# bqZUM_UsbBtAdapter.net
KiCad netlist of a schematic drawn in Altium Designer
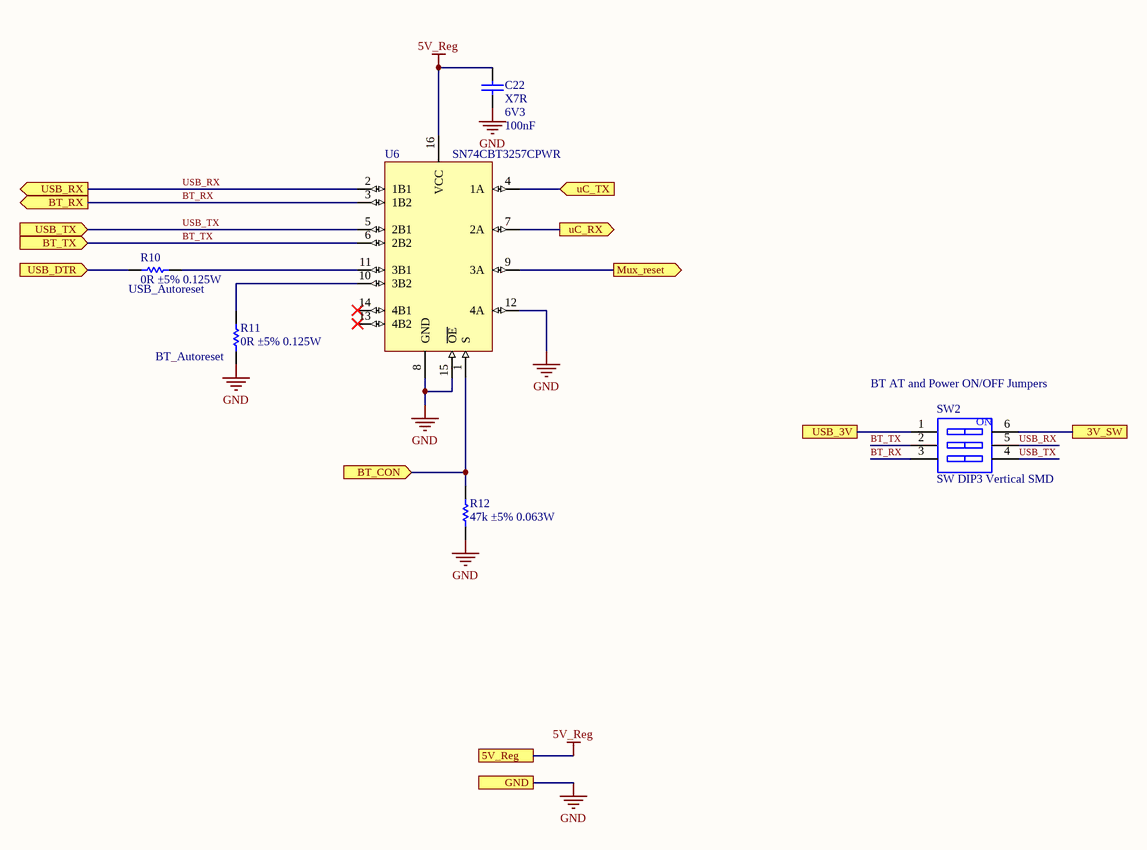
[diagram p0: bqZUM_UsbBtAdapter.SchDoc]

(export (version "E")
  (design (tool "Eeschema 10.0.6"))
  (components
    (comp (ref "C22")
      (value "Capacitor")
      (footprint "C0402")
      (fields
        (field (name "DIELECTRIC") "X7R")
        (field (name "VOLTAGE") "6V3")
        (field (name "CAPACITANCE") "100nF")
        (field (name "PART NUMBER") "C0402_100nF_6V3_±10%")
        (field (name "TOLERANCE") "±10%")
        (field (name "MANUFACTURER") "Kemet")
      )
      (libsource (lib "Pasives_Capacitor_SMD") (part "Capacitor"))
    )
    (comp (ref "R10")
      (value "0R ±5% 0.125W")
      (footprint "R0805")
      (description "Resistor")
      (fields (field (name "TOLERANCE") "±5%") (field (name "POWER") "0.125W"))
      (libsource (lib "Pasives_Resistor_SMD") (part "Resistor"))
    )
    (comp (ref "R11")
      (value "0R ±5% 0.125W")
      (footprint "R0805")
      (description "Resistor")
      (fields (field (name "TOLERANCE") "±5%") (field (name "POWER") "0.125W"))
      (libsource (lib "Pasives_Resistor_SMD") (part "Resistor"))
    )
    (comp (ref "R12")
      (value "47k ±5% 0.063W")
      (footprint "R0402")
      (description "Resistor")
      (fields (field (name "TOLERANCE") "±5%") (field (name "POWER") "0.063W"))
      (libsource (lib "Pasives_Resistor_SMD") (part "Resistor"))
    )
    (comp (ref "SW2")
      (value "SW DIP3 Vertical SMD")
      (footprint "SW DIP3 SMD 1.27")
      (description "SWITCH TAPE SEAL 3 POS SMD")
      (fields (field (name "PART NUMBER") "SW-DIP 3 SMD") (field (name "MANUFACTURER") "Würth Elektronik"))
      (libsource (lib "Electromechanical") (part "SW DIP3 Vertical SMD"))
    )
    (comp (ref "U6")
      (value "SN74CBT3257CPWR")
      (footprint "TSSOP16")
      (description "4-bit 1-of-2 FET multiplexer/demultiplexer")
      (fields (field (name "PART NUMBER") "SN74CBT3257") (field (name "MANUFACTURER") "Texas Instruments"))
      (libsource (lib "Semiconductors_Logic_Gate") (part "SN74CBT3257"))
    )
  )
  (nets
    (net (code "1") (name "/3V_SW") (class "Default")
      (node (ref "SW2") (pin "6") (pinfunction "6_6") (pintype "passive"))
    )
    (net (code "2") (name "/BT_CON") (class "Default")
      (node (ref "R12") (pin "2") (pinfunction "2_2") (pintype "passive"))
      (node (ref "U6") (pin "1") (pinfunction "S_1") (pintype "input"))
    )
    (net (code "3") (name "/BT_RX") (class "Default")
      (node (ref "SW2") (pin "3") (pinfunction "3_3") (pintype "passive"))
      (node (ref "U6") (pin "3") (pinfunction "1B2_3") (pintype "bidirectional"))
    )
    (net (code "4") (name "/BT_TX") (class "Default")
      (node (ref "SW2") (pin "2") (pinfunction "2_2") (pintype "passive"))
      (node (ref "U6") (pin "6") (pinfunction "2B2_6") (pintype "bidirectional"))
    )
    (net (code "5") (name "/Mux_reset") (class "Default")
      (node (ref "U6") (pin "9") (pinfunction "3A_9") (pintype "bidirectional"))
    )
    (net (code "6") (name "/USB_3V") (class "Default")
      (node (ref "SW2") (pin "1") (pinfunction "1_1") (pintype "passive"))
    )
    (net (code "7") (name "/USB_DTR") (class "Default")
      (node (ref "R10") (pin "1") (pinfunction "1_1") (pintype "passive"))
    )
    (net (code "8") (name "/USB_RX") (class "Default")
      (node (ref "SW2") (pin "5") (pinfunction "5_5") (pintype "passive"))
      (node (ref "U6") (pin "2") (pinfunction "1B1_2") (pintype "bidirectional"))
    )
    (net (code "9") (name "/USB_TX") (class "Default")
      (node (ref "SW2") (pin "4") (pinfunction "4_4") (pintype "passive"))
      (node (ref "U6") (pin "5") (pinfunction "2B1_5") (pintype "bidirectional"))
    )
    (net (code "10") (name "/uC_RX") (class "Default")
      (node (ref "U6") (pin "7") (pinfunction "2A_7") (pintype "bidirectional"))
    )
    (net (code "11") (name "/uC_TX") (class "Default")
      (node (ref "U6") (pin "4") (pinfunction "1A_4") (pintype "bidirectional"))
    )
    (net (code "12") (name "5V_Reg") (class "Default")
      (node (ref "C22") (pin "1") (pinfunction "1_1") (pintype "passive"))
      (node (ref "U6") (pin "16") (pinfunction "VCC_16") (pintype "power_in"))
    )
    (net (code "13") (name "GND") (class "Default")
      (node (ref "C22") (pin "2") (pinfunction "2_2") (pintype "passive"))
      (node (ref "R11") (pin "1") (pinfunction "1_1") (pintype "passive"))
      (node (ref "R12") (pin "1") (pinfunction "1_1") (pintype "passive"))
      (node (ref "U6") (pin "12") (pinfunction "4A_12") (pintype "bidirectional"))
      (node (ref "U6") (pin "15") (pinfunction "~{OE}_15") (pintype "input"))
      (node (ref "U6") (pin "8") (pinfunction "GND_8") (pintype "power_in"))
    )
    (net (code "14") (name "Net-(U6-3B1)") (class "Default")
      (node (ref "R10") (pin "2") (pinfunction "2_2") (pintype "passive"))
      (node (ref "U6") (pin "11") (pinfunction "3B1_11") (pintype "bidirectional"))
    )
    (net (code "15") (name "Net-(U6-3B2)") (class "Default")
      (node (ref "R11") (pin "2") (pinfunction "2_2") (pintype "passive"))
      (node (ref "U6") (pin "10") (pinfunction "3B2_10") (pintype "bidirectional"))
    )
    (net (code "16") (name "unconnected-(U6-4B1-Pad14)") (class "Default")
      (node (ref "U6") (pin "14") (pinfunction "4B1_14") (pintype "bidirectional+no_connect"))
    )
    (net (code "17") (name "unconnected-(U6-4B2-Pad13)") (class "Default")
      (node (ref "U6") (pin "13") (pinfunction "4B2_13") (pintype "bidirectional+no_connect"))
    )
  )
)
